# Pixel1_0_2.net
KiCad netlist of a schematic drawn in Altium Designer
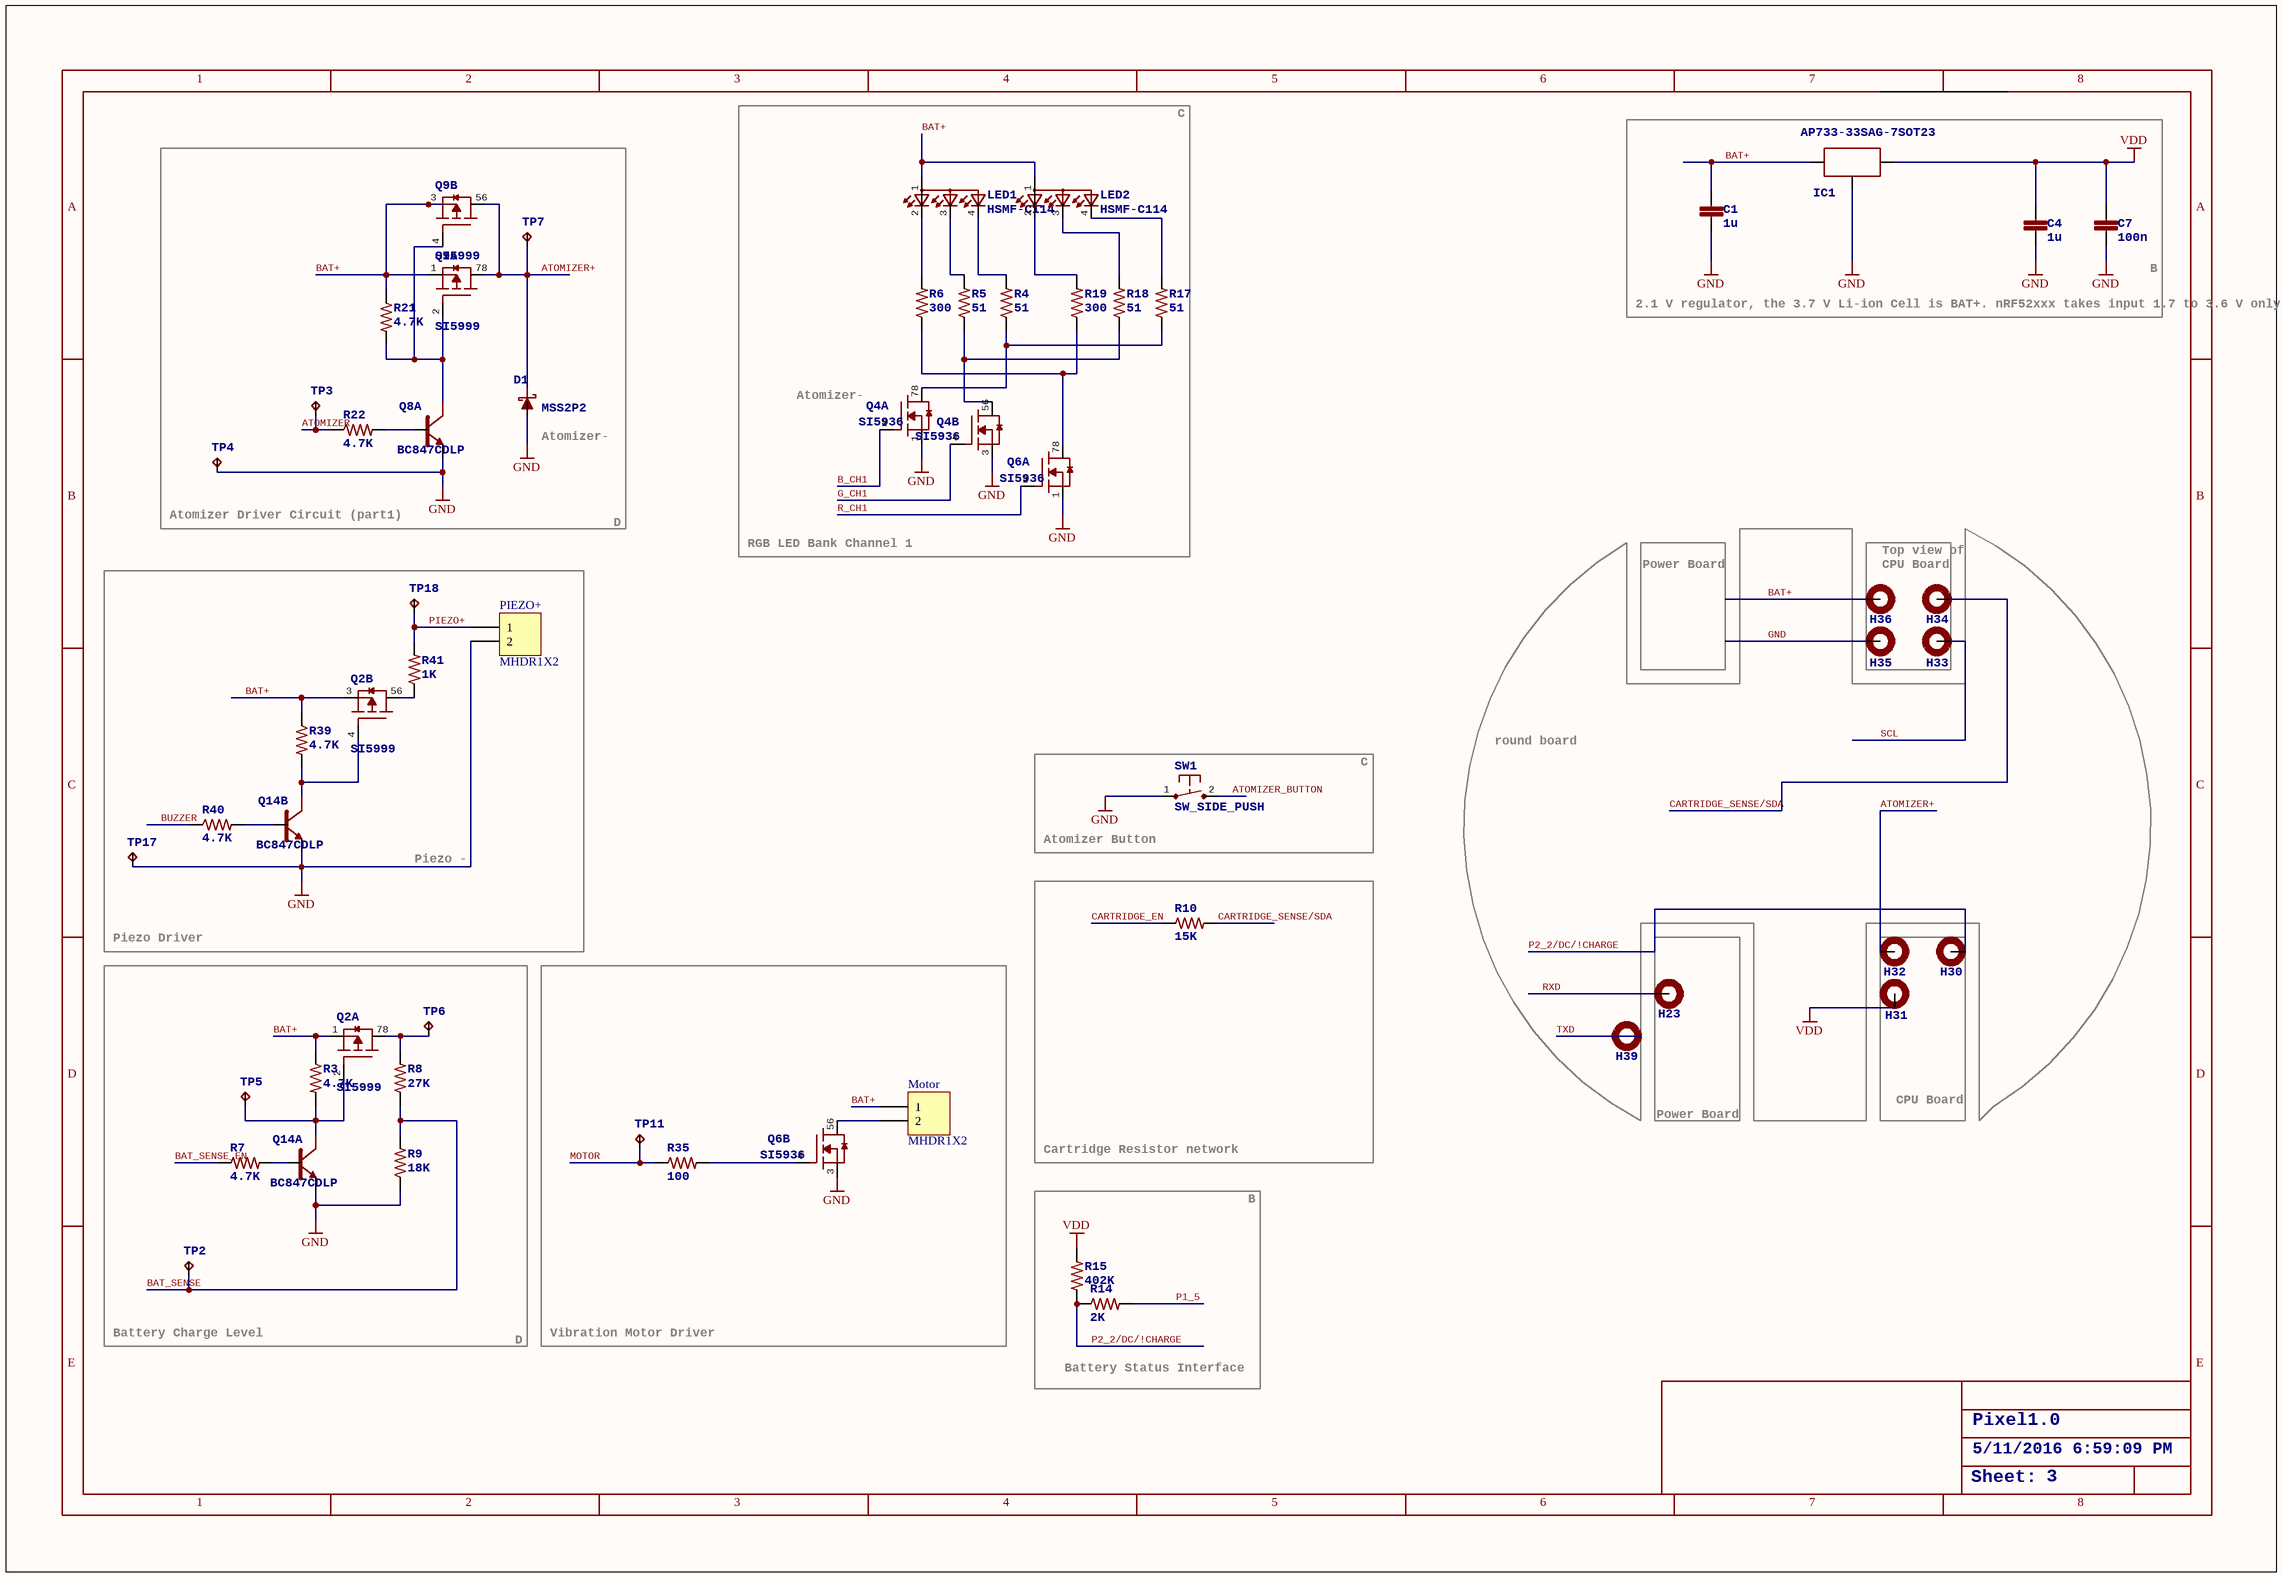
[diagram p0: Pixel1.0_2.SchDoc]

(export (version "E")
  (design (tool "Eeschema 10.0.6"))
  (components
    (comp (ref "C1")
      (value "1u")
      (footprint "C0603")
      (description "CAPACITOR, European symbol")
      (libsource (lib "rcl") (part "C-EUC0603"))
    )
    (comp (ref "C4")
      (value "1u")
      (footprint "C0603")
      (description "CAPACITOR, European symbol")
      (libsource (lib "rcl") (part "C-EUC0603"))
    )
    (comp (ref "C7")
      (value "100n")
      (footprint "C0603")
      (description "CAPACITOR, European symbol")
      (libsource (lib "rcl") (part "C-EUC0603"))
    )
    (comp (ref "D1") (value "MSS2P2") (footprint "MICROSMP") (libsource (lib "vapeix") (part "MSS2P2")))
    (comp (ref "H23")
      (value "MOUNT-PAD-ROUND1.5MMX1MM")
      (footprint "TMOUNT4")
      (description "MOUNTING PAD, round")
      (libsource (lib "Pixel1.0") (part "MOUNT-PAD-ROUND1.5MMX1MM"))
    )
    (comp (ref "H30")
      (value "MOUNT-PAD-ROUNDTMOUNT1")
      (footprint "T-MOUNT1")
      (description "MOUNTING PAD, round")
      (libsource (lib "Pixel1.0") (part "MOUNT-PAD-ROUNDTMOUNT1"))
    )
    (comp (ref "H31")
      (value "MOUNT-PAD-ROUNDTMOUNT1")
      (footprint "T-MOUNT1")
      (description "MOUNTING PAD, round")
      (libsource (lib "Pixel1.0") (part "MOUNT-PAD-ROUNDTMOUNT1"))
    )
    (comp (ref "H32")
      (value "MOUNT-PAD-ROUNDTMOUNT1")
      (footprint "T-MOUNT1")
      (description "MOUNTING PAD, round")
      (libsource (lib "Pixel1.0") (part "MOUNT-PAD-ROUNDTMOUNT1"))
    )
    (comp (ref "H33")
      (value "MOUNT-PAD-ROUNDTMOUNT1")
      (footprint "T-MOUNT1")
      (description "MOUNTING PAD, round")
      (libsource (lib "Pixel1.0") (part "MOUNT-PAD-ROUNDTMOUNT1"))
    )
    (comp (ref "H34")
      (value "MOUNT-PAD-ROUNDTMOUNT1")
      (footprint "T-MOUNT1")
      (description "MOUNTING PAD, round")
      (libsource (lib "Pixel1.0") (part "MOUNT-PAD-ROUNDTMOUNT1"))
    )
    (comp (ref "H35")
      (value "MOUNT-PAD-ROUNDTMOUNT1")
      (footprint "T-MOUNT1")
      (description "MOUNTING PAD, round")
      (libsource (lib "Pixel1.0") (part "MOUNT-PAD-ROUNDTMOUNT1"))
    )
    (comp (ref "H36")
      (value "MOUNT-PAD-ROUNDTMOUNT1")
      (footprint "T-MOUNT1")
      (description "MOUNTING PAD, round")
      (libsource (lib "Pixel1.0") (part "MOUNT-PAD-ROUNDTMOUNT1"))
    )
    (comp (ref "H39")
      (value "MOUNT-PAD-ROUND1.5MMX1MM")
      (footprint "TMOUNT4")
      (description "MOUNTING PAD, round")
      (libsource (lib "Pixel1.0") (part "MOUNT-PAD-ROUND1.5MMX1MM"))
    )
    (comp (ref "IC1")
      (value "AP733-33SAG-7SOT23")
      (footprint "SOT23")
      (libsource (lib "vapeix") (part "AP733-33SAG-7SOT23"))
    )
    (comp (ref "LED1")
      (value "HSMF-C114")
      (footprint "HSMFC114")
      (description "Chip LED RGB   Source: http://document.sharpsma.com/files/GM1WA55311A_SS.pdf")
      (libsource (lib "vapeix") (part "HSMF-C114"))
    )
    (comp (ref "LED2")
      (value "HSMF-C114")
      (footprint "HSMFC114")
      (description "Chip LED RGB   Source: http://document.sharpsma.com/files/GM1WA55311A_SS.pdf")
      (libsource (lib "vapeix") (part "HSMF-C114"))
    )
    (comp (ref "Motor")
      (value "MHDR1X2")
      (footprint "MHDR1X2")
      (description "Header, 2-Pin")
      (fields (field (name "PUBLISHER") "Altium Limited"))
      (libsource (lib "Miscellaneous Connectors") (part "MHDR1X2"))
    )
    (comp (ref "PIEZO+")
      (value "MHDR1X2")
      (footprint "MHDR1X2")
      (description "Header, 2-Pin")
      (fields (field (name "PUBLISHER") "Altium Limited"))
      (libsource (lib "Miscellaneous Connectors") (part "MHDR1X2"))
    )
    (comp (ref "Q2")
      (value "SI5999")
      (footprint "1206-8CHIP-FET")
      (description "Dual N-Channel 30-V (D-S) MOSFET   Source: http://www.vishay.com/docs/71053/71053.pdf")
      (libsource (lib "Pixel1.0") (part "SI5999"))
    )
    (comp (ref "Q4")
      (value "SI5936")
      (footprint "1206-8CHIP-FET")
      (libsource (lib "Pixel1.0") (part "SI5936"))
    )
    (comp (ref "Q6")
      (value "SI5936")
      (footprint "1206-8CHIP-FET")
      (libsource (lib "Pixel1.0") (part "SI5936"))
    )
    (comp (ref "Q8")
      (value "BC847CDLP")
      (footprint "X2-DFN1310-6")
      (description "http://www.diodes.com/datasheets/ds30817.pdf")
      (libsource (lib "vapeix") (part "BC847CDLP"))
    )
    (comp (ref "Q9")
      (value "SI5999")
      (footprint "1206-8CHIP-FET")
      (description "Dual N-Channel 30-V (D-S) MOSFET   Source: http://www.vishay.com/docs/71053/71053.pdf")
      (libsource (lib "Pixel1.0") (part "SI5999"))
    )
    (comp (ref "Q14")
      (value "BC847CDLP")
      (footprint "X2-DFN1310-6")
      (description "http://www.diodes.com/datasheets/ds30817.pdf")
      (libsource (lib "vapeix") (part "BC847CDLP"))
    )
    (comp (ref "R3")
      (value "4.7K")
      (footprint "R0201")
      (description "RESISTOR, American symbol")
      (libsource (lib "rcl") (part "R-US_R0201"))
    )
    (comp (ref "R4")
      (value "51")
      (footprint "R0201")
      (description "RESISTOR, American symbol")
      (libsource (lib "rcl") (part "R-US_R0201"))
    )
    (comp (ref "R5")
      (value "51")
      (footprint "R0201")
      (description "RESISTOR, American symbol")
      (libsource (lib "rcl") (part "R-US_R0201"))
    )
    (comp (ref "R6")
      (value "300")
      (footprint "R0201")
      (description "RESISTOR, American symbol")
      (libsource (lib "rcl") (part "R-US_R0201"))
    )
    (comp (ref "R7")
      (value "4.7K")
      (footprint "R0201")
      (description "RESISTOR, American symbol")
      (libsource (lib "rcl") (part "R-US_R0201"))
    )
    (comp (ref "R8")
      (value "27K")
      (footprint "R0201")
      (description "RESISTOR, American symbol")
      (libsource (lib "rcl") (part "R-US_R0201"))
    )
    (comp (ref "R9")
      (value "18K")
      (footprint "R0201")
      (description "RESISTOR, American symbol")
      (libsource (lib "rcl") (part "R-US_R0201"))
    )
    (comp (ref "R10")
      (value "15K")
      (footprint "R0201")
      (description "RESISTOR, American symbol")
      (libsource (lib "rcl") (part "R-US_R0201"))
    )
    (comp (ref "R14")
      (value "2K")
      (footprint "R0201")
      (description "RESISTOR, American symbol")
      (libsource (lib "rcl") (part "R-US_R0201"))
    )
    (comp (ref "R15")
      (value "402K")
      (footprint "R0201")
      (description "RESISTOR, American symbol")
      (libsource (lib "rcl") (part "R-US_R0201"))
    )
    (comp (ref "R17")
      (value "51")
      (footprint "R0201")
      (description "RESISTOR, American symbol")
      (libsource (lib "rcl") (part "R-US_R0201"))
    )
    (comp (ref "R18")
      (value "51")
      (footprint "R0201")
      (description "RESISTOR, American symbol")
      (libsource (lib "rcl") (part "R-US_R0201"))
    )
    (comp (ref "R19")
      (value "300")
      (footprint "R0201")
      (description "RESISTOR, American symbol")
      (libsource (lib "rcl") (part "R-US_R0201"))
    )
    (comp (ref "R21")
      (value "4.7K")
      (footprint "R0201")
      (description "RESISTOR, American symbol")
      (libsource (lib "rcl") (part "R-US_R0201"))
    )
    (comp (ref "R22")
      (value "4.7K")
      (footprint "R0201")
      (description "RESISTOR, American symbol")
      (libsource (lib "rcl") (part "R-US_R0201"))
    )
    (comp (ref "R35")
      (value "100")
      (footprint "R0201")
      (description "RESISTOR, American symbol")
      (libsource (lib "rcl") (part "R-US_R0201"))
    )
    (comp (ref "R39")
      (value "4.7K")
      (footprint "R0201")
      (description "RESISTOR, American symbol")
      (libsource (lib "rcl") (part "R-US_R0201"))
    )
    (comp (ref "R40")
      (value "4.7K")
      (footprint "R0201")
      (description "RESISTOR, American symbol")
      (libsource (lib "rcl") (part "R-US_R0201"))
    )
    (comp (ref "R41")
      (value "1K")
      (footprint "R0201")
      (description "RESISTOR, American symbol")
      (libsource (lib "rcl") (part "R-US_R0201"))
    )
    (comp (ref "SW1")
      (value "SW_SIDE_PUSH")
      (footprint "SW1")
      (libsource (lib "vapeix") (part "SW_SIDE_PUSH"))
    )
    (comp (ref "TP2")
      (value "TPTP06R")
      (footprint "TP06R")
      (description "Test pad")
      (libsource (lib "testpad") (part "TPTP06R"))
    )
    (comp (ref "TP3")
      (value "TPTP06R")
      (footprint "TP06R")
      (description "Test pad")
      (libsource (lib "testpad") (part "TPTP06R"))
    )
    (comp (ref "TP4")
      (value "TPTP06R")
      (footprint "TP06R")
      (description "Test pad")
      (libsource (lib "testpad") (part "TPTP06R"))
    )
    (comp (ref "TP5")
      (value "TPTP06R")
      (footprint "TP06R")
      (description "Test pad")
      (libsource (lib "testpad") (part "TPTP06R"))
    )
    (comp (ref "TP6")
      (value "TPTP06R")
      (footprint "TP06R")
      (description "Test pad")
      (libsource (lib "testpad") (part "TPTP06R"))
    )
    (comp (ref "TP7")
      (value "TPTP06R")
      (footprint "TP06R")
      (description "Test pad")
      (libsource (lib "testpad") (part "TPTP06R"))
    )
    (comp (ref "TP11")
      (value "TPTP06R")
      (footprint "TP06R")
      (description "Test pad")
      (libsource (lib "testpad") (part "TPTP06R"))
    )
    (comp (ref "TP17")
      (value "TPTP06R")
      (footprint "TP06R")
      (description "Test pad")
      (libsource (lib "testpad") (part "TPTP06R"))
    )
    (comp (ref "TP18")
      (value "TPTP06R")
      (footprint "TP06R")
      (description "Test pad")
      (libsource (lib "testpad") (part "TPTP06R"))
    )
  )
  (nets
    (net (code "1") (name "/ATOMIZER") (class "Default")
      (node (ref "R22") (pin "1") (pinfunction "1_1") (pintype "passive"))
      (node (ref "TP3") (pin "TP") (pinfunction "TP_TP") (pintype "passive"))
    )
    (net (code "2") (name "/ATOMIZER+") (class "Default")
      (node (ref "D1") (pin "K") (pinfunction "K_K") (pintype "passive"))
      (node (ref "H32") (pin "1") (pinfunction "MOUNT_1") (pintype "passive"))
      (node (ref "Q9") (pin "56") (pinfunction "D2_56") (pintype "passive"))
      (node (ref "Q9") (pin "78") (pinfunction "D1_78") (pintype "passive"))
      (node (ref "TP7") (pin "TP") (pinfunction "TP_TP") (pintype "passive"))
    )
    (net (code "3") (name "/ATOMIZER_BUTTON") (class "Default")
      (node (ref "SW1") (pin "2") (pinfunction "S_2") (pintype "passive"))
    )
    (net (code "4") (name "/BAT+") (class "Default")
      (node (ref "C1") (pin "2") (pinfunction "2_2") (pintype "passive"))
      (node (ref "H36") (pin "1") (pinfunction "MOUNT_1") (pintype "passive"))
      (node (ref "IC1") (pin "1") (pinfunction "IN_1") (pintype "passive"))
      (node (ref "LED1") (pin "1") (pinfunction "A_1") (pintype "passive"))
      (node (ref "LED2") (pin "1") (pinfunction "A_1") (pintype "passive"))
      (node (ref "Motor") (pin "1") (pinfunction "1_1") (pintype "passive"))
      (node (ref "Q2") (pin "1") (pinfunction "S1_1") (pintype "passive"))
      (node (ref "Q2") (pin "3") (pinfunction "S2_3") (pintype "passive"))
      (node (ref "Q9") (pin "1") (pinfunction "S1_1") (pintype "passive"))
      (node (ref "Q9") (pin "3") (pinfunction "S2_3") (pintype "passive"))
      (node (ref "R21") (pin "1") (pinfunction "1_1") (pintype "passive"))
      (node (ref "R3") (pin "1") (pinfunction "1_1") (pintype "passive"))
      (node (ref "R39") (pin "1") (pinfunction "1_1") (pintype "passive"))
    )
    (net (code "5") (name "/BAT_SENSE") (class "Default")
      (node (ref "R8") (pin "1") (pinfunction "1_1") (pintype "passive"))
      (node (ref "R9") (pin "2") (pinfunction "2_2") (pintype "passive"))
      (node (ref "TP2") (pin "TP") (pinfunction "TP_TP") (pintype "passive"))
    )
    (net (code "6") (name "/BAT_SENSE_EN") (class "Default")
      (node (ref "R7") (pin "1") (pinfunction "1_1") (pintype "passive"))
    )
    (net (code "7") (name "/BUZZER") (class "Default")
      (node (ref "R40") (pin "1") (pinfunction "1_1") (pintype "passive"))
    )
    (net (code "8") (name "/B_CH1") (class "Default")
      (node (ref "Q4") (pin "2") (pinfunction "G1_2") (pintype "passive"))
    )
    (net (code "9") (name "/CARTRIDGE_EN") (class "Default")
      (node (ref "R10") (pin "1") (pinfunction "1_1") (pintype "passive"))
    )
    (net (code "10") (name "/CARTRIDGE_SENSE{slash}SDA") (class "Default")
      (node (ref "H34") (pin "1") (pinfunction "MOUNT_1") (pintype "passive"))
      (node (ref "R10") (pin "2") (pinfunction "2_2") (pintype "passive"))
    )
    (net (code "11") (name "/G_CH1") (class "Default")
      (node (ref "Q4") (pin "4") (pinfunction "G2_4") (pintype "passive"))
    )
    (net (code "12") (name "/MOTOR") (class "Default")
      (node (ref "R35") (pin "1") (pinfunction "1_1") (pintype "passive"))
      (node (ref "TP11") (pin "TP") (pinfunction "TP_TP") (pintype "passive"))
    )
    (net (code "13") (name "/P1_5") (class "Default")
      (node (ref "R14") (pin "2") (pinfunction "2_2") (pintype "passive"))
    )
    (net (code "14") (name "/P2_2{slash}DC{slash}!CHARGE") (class "Default")
      (node (ref "H30") (pin "1") (pinfunction "MOUNT_1") (pintype "passive"))
      (node (ref "R14") (pin "1") (pinfunction "1_1") (pintype "passive"))
      (node (ref "R15") (pin "2") (pinfunction "2_2") (pintype "passive"))
    )
    (net (code "15") (name "/PIEZO+") (class "Default")
      (node (ref "PIEZO+") (pin "1") (pinfunction "1_1") (pintype "passive"))
      (node (ref "R41") (pin "2") (pinfunction "2_2") (pintype "passive"))
      (node (ref "TP18") (pin "TP") (pinfunction "TP_TP") (pintype "passive"))
    )
    (net (code "16") (name "/RXD") (class "Default")
      (node (ref "H23") (pin "1") (pinfunction "MOUNT_1") (pintype "passive"))
    )
    (net (code "17") (name "/R_CH1") (class "Default")
      (node (ref "Q6") (pin "2") (pinfunction "G1_2") (pintype "passive"))
    )
    (net (code "18") (name "/SCL") (class "Default")
      (node (ref "H33") (pin "1") (pinfunction "MOUNT_1") (pintype "passive"))
    )
    (net (code "19") (name "/TXD") (class "Default")
      (node (ref "H39") (pin "1") (pinfunction "MOUNT_1") (pintype "passive"))
    )
    (net (code "20") (name "GND") (class "Default")
      (node (ref "C1") (pin "1") (pinfunction "1_1") (pintype "passive"))
      (node (ref "C4") (pin "1") (pinfunction "1_1") (pintype "passive"))
      (node (ref "C7") (pin "1") (pinfunction "1_1") (pintype "passive"))
      (node (ref "D1") (pin "A") (pinfunction "A_A") (pintype "passive"))
      (node (ref "H35") (pin "1") (pinfunction "MOUNT_1") (pintype "passive"))
      (node (ref "IC1") (pin "3") (pinfunction "GND_3") (pintype "passive"))
      (node (ref "PIEZO+") (pin "2") (pinfunction "2_2") (pintype "passive"))
      (node (ref "Q14") (pin "E1") (pinfunction "E_E1") (pintype "passive"))
      (node (ref "Q14") (pin "E2") (pinfunction "E_E2") (pintype "passive"))
      (node (ref "Q4") (pin "1") (pinfunction "S1_1") (pintype "passive"))
      (node (ref "Q4") (pin "3") (pinfunction "S2_3") (pintype "passive"))
      (node (ref "Q6") (pin "1") (pinfunction "S1_1") (pintype "passive"))
      (node (ref "Q6") (pin "3") (pinfunction "S2_3") (pintype "passive"))
      (node (ref "Q8") (pin "E1") (pinfunction "E_E1") (pintype "passive"))
      (node (ref "R9") (pin "1") (pinfunction "1_1") (pintype "passive"))
      (node (ref "SW1") (pin "1") (pinfunction "P_1") (pintype "passive"))
      (node (ref "TP17") (pin "TP") (pinfunction "TP_TP") (pintype "passive"))
      (node (ref "TP4") (pin "TP") (pinfunction "TP_TP") (pintype "passive"))
    )
    (net (code "21") (name "Net-(LED1-BLUE)") (class "Default")
      (node (ref "LED1") (pin "4") (pinfunction "BLUE_4") (pintype "passive"))
      (node (ref "R4") (pin "2") (pinfunction "2_2") (pintype "passive"))
    )
    (net (code "22") (name "Net-(LED1-GREEN)") (class "Default")
      (node (ref "LED1") (pin "3") (pinfunction "GREEN_3") (pintype "passive"))
      (node (ref "R5") (pin "2") (pinfunction "2_2") (pintype "passive"))
    )
    (net (code "23") (name "Net-(LED1-RED)") (class "Default")
      (node (ref "LED1") (pin "2") (pinfunction "RED_2") (pintype "passive"))
      (node (ref "R6") (pin "2") (pinfunction "2_2") (pintype "passive"))
    )
    (net (code "24") (name "Net-(LED2-BLUE)") (class "Default")
      (node (ref "LED2") (pin "4") (pinfunction "BLUE_4") (pintype "passive"))
      (node (ref "R17") (pin "2") (pinfunction "2_2") (pintype "passive"))
    )
    (net (code "25") (name "Net-(LED2-GREEN)") (class "Default")
      (node (ref "LED2") (pin "3") (pinfunction "GREEN_3") (pintype "passive"))
      (node (ref "R18") (pin "2") (pinfunction "2_2") (pintype "passive"))
    )
    (net (code "26") (name "Net-(LED2-RED)") (class "Default")
      (node (ref "LED2") (pin "2") (pinfunction "RED_2") (pintype "passive"))
      (node (ref "R19") (pin "2") (pinfunction "2_2") (pintype "passive"))
    )
    (net (code "27") (name "Net-(Q2A-D1)") (class "Default")
      (node (ref "Q2") (pin "78") (pinfunction "D1_78") (pintype "passive"))
      (node (ref "R8") (pin "2") (pinfunction "2_2") (pintype "passive"))
      (node (ref "TP6") (pin "TP") (pinfunction "TP_TP") (pintype "passive"))
    )
    (net (code "28") (name "Net-(Q2B-D2)") (class "Default")
      (node (ref "Q2") (pin "56") (pinfunction "D2_56") (pintype "passive"))
      (node (ref "R41") (pin "1") (pinfunction "1_1") (pintype "passive"))
    )
    (net (code "29") (name "Net-(Q4A-D1)") (class "Default")
      (node (ref "Q4") (pin "78") (pinfunction "D1_78") (pintype "passive"))
      (node (ref "R17") (pin "1") (pinfunction "1_1") (pintype "passive"))
      (node (ref "R4") (pin "1") (pinfunction "1_1") (pintype "passive"))
    )
    (net (code "30") (name "Net-(Q4B-D2)") (class "Default")
      (node (ref "Q4") (pin "56") (pinfunction "D2_56") (pintype "passive"))
      (node (ref "R18") (pin "1") (pinfunction "1_1") (pintype "passive"))
      (node (ref "R5") (pin "1") (pinfunction "1_1") (pintype "passive"))
    )
    (net (code "31") (name "Net-(Q6A-D1)") (class "Default")
      (node (ref "Q6") (pin "78") (pinfunction "D1_78") (pintype "passive"))
      (node (ref "R19") (pin "1") (pinfunction "1_1") (pintype "passive"))
      (node (ref "R6") (pin "1") (pinfunction "1_1") (pintype "passive"))
    )
    (net (code "32") (name "Net-(Q6B-D2)") (class "Default")
      (node (ref "Motor") (pin "2") (pinfunction "2_2") (pintype "passive"))
      (node (ref "Q6") (pin "56") (pinfunction "D2_56") (pintype "passive"))
    )
    (net (code "33") (name "Net-(Q6B-G2)") (class "Default")
      (node (ref "Q6") (pin "4") (pinfunction "G2_4") (pintype "passive"))
      (node (ref "R35") (pin "2") (pinfunction "2_2") (pintype "passive"))
    )
    (net (code "34") (name "Net-(Q8A-B)") (class "Default")
      (node (ref "Q8") (pin "B1") (pinfunction "B_B1") (pintype "passive"))
      (node (ref "R22") (pin "2") (pinfunction "2_2") (pintype "passive"))
    )
    (net (code "35") (name "Net-(Q8A-C)") (class "Default")
      (node (ref "Q8") (pin "C1") (pinfunction "C_C1") (pintype "passive"))
      (node (ref "Q9") (pin "2") (pinfunction "G1_2") (pintype "passive"))
      (node (ref "Q9") (pin "4") (pinfunction "G2_4") (pintype "passive"))
      (node (ref "R21") (pin "2") (pinfunction "2_2") (pintype "passive"))
    )
    (net (code "36") (name "Net-(Q14A-B)") (class "Default")
      (node (ref "Q14") (pin "B1") (pinfunction "B_B1") (pintype "passive"))
      (node (ref "R7") (pin "2") (pinfunction "2_2") (pintype "passive"))
    )
    (net (code "37") (name "Net-(Q14A-C)") (class "Default")
      (node (ref "Q14") (pin "C1") (pinfunction "C_C1") (pintype "passive"))
      (node (ref "Q2") (pin "2") (pinfunction "G1_2") (pintype "passive"))
      (node (ref "R3") (pin "2") (pinfunction "2_2") (pintype "passive"))
      (node (ref "TP5") (pin "TP") (pinfunction "TP_TP") (pintype "passive"))
    )
    (net (code "38") (name "Net-(Q14B-B)") (class "Default")
      (node (ref "Q14") (pin "B2") (pinfunction "B_B2") (pintype "passive"))
      (node (ref "R40") (pin "2") (pinfunction "2_2") (pintype "passive"))
    )
    (net (code "39") (name "Net-(Q14B-C)") (class "Default")
      (node (ref "Q14") (pin "C2") (pinfunction "C_C2") (pintype "passive"))
      (node (ref "Q2") (pin "4") (pinfunction "G2_4") (pintype "passive"))
      (node (ref "R39") (pin "2") (pinfunction "2_2") (pintype "passive"))
    )
    (net (code "40") (name "VDD") (class "Default")
      (node (ref "C4") (pin "2") (pinfunction "2_2") (pintype "passive"))
      (node (ref "C7") (pin "2") (pinfunction "2_2") (pintype "passive"))
      (node (ref "H31") (pin "1") (pinfunction "MOUNT_1") (pintype "passive"))
      (node (ref "IC1") (pin "2") (pinfunction "OUT_2") (pintype "passive"))
      (node (ref "R15") (pin "1") (pinfunction "1_1") (pintype "passive"))
    )
  )
)
